# SCU_PCIe.net
KiCad netlist of a schematic drawn in Altium Designer
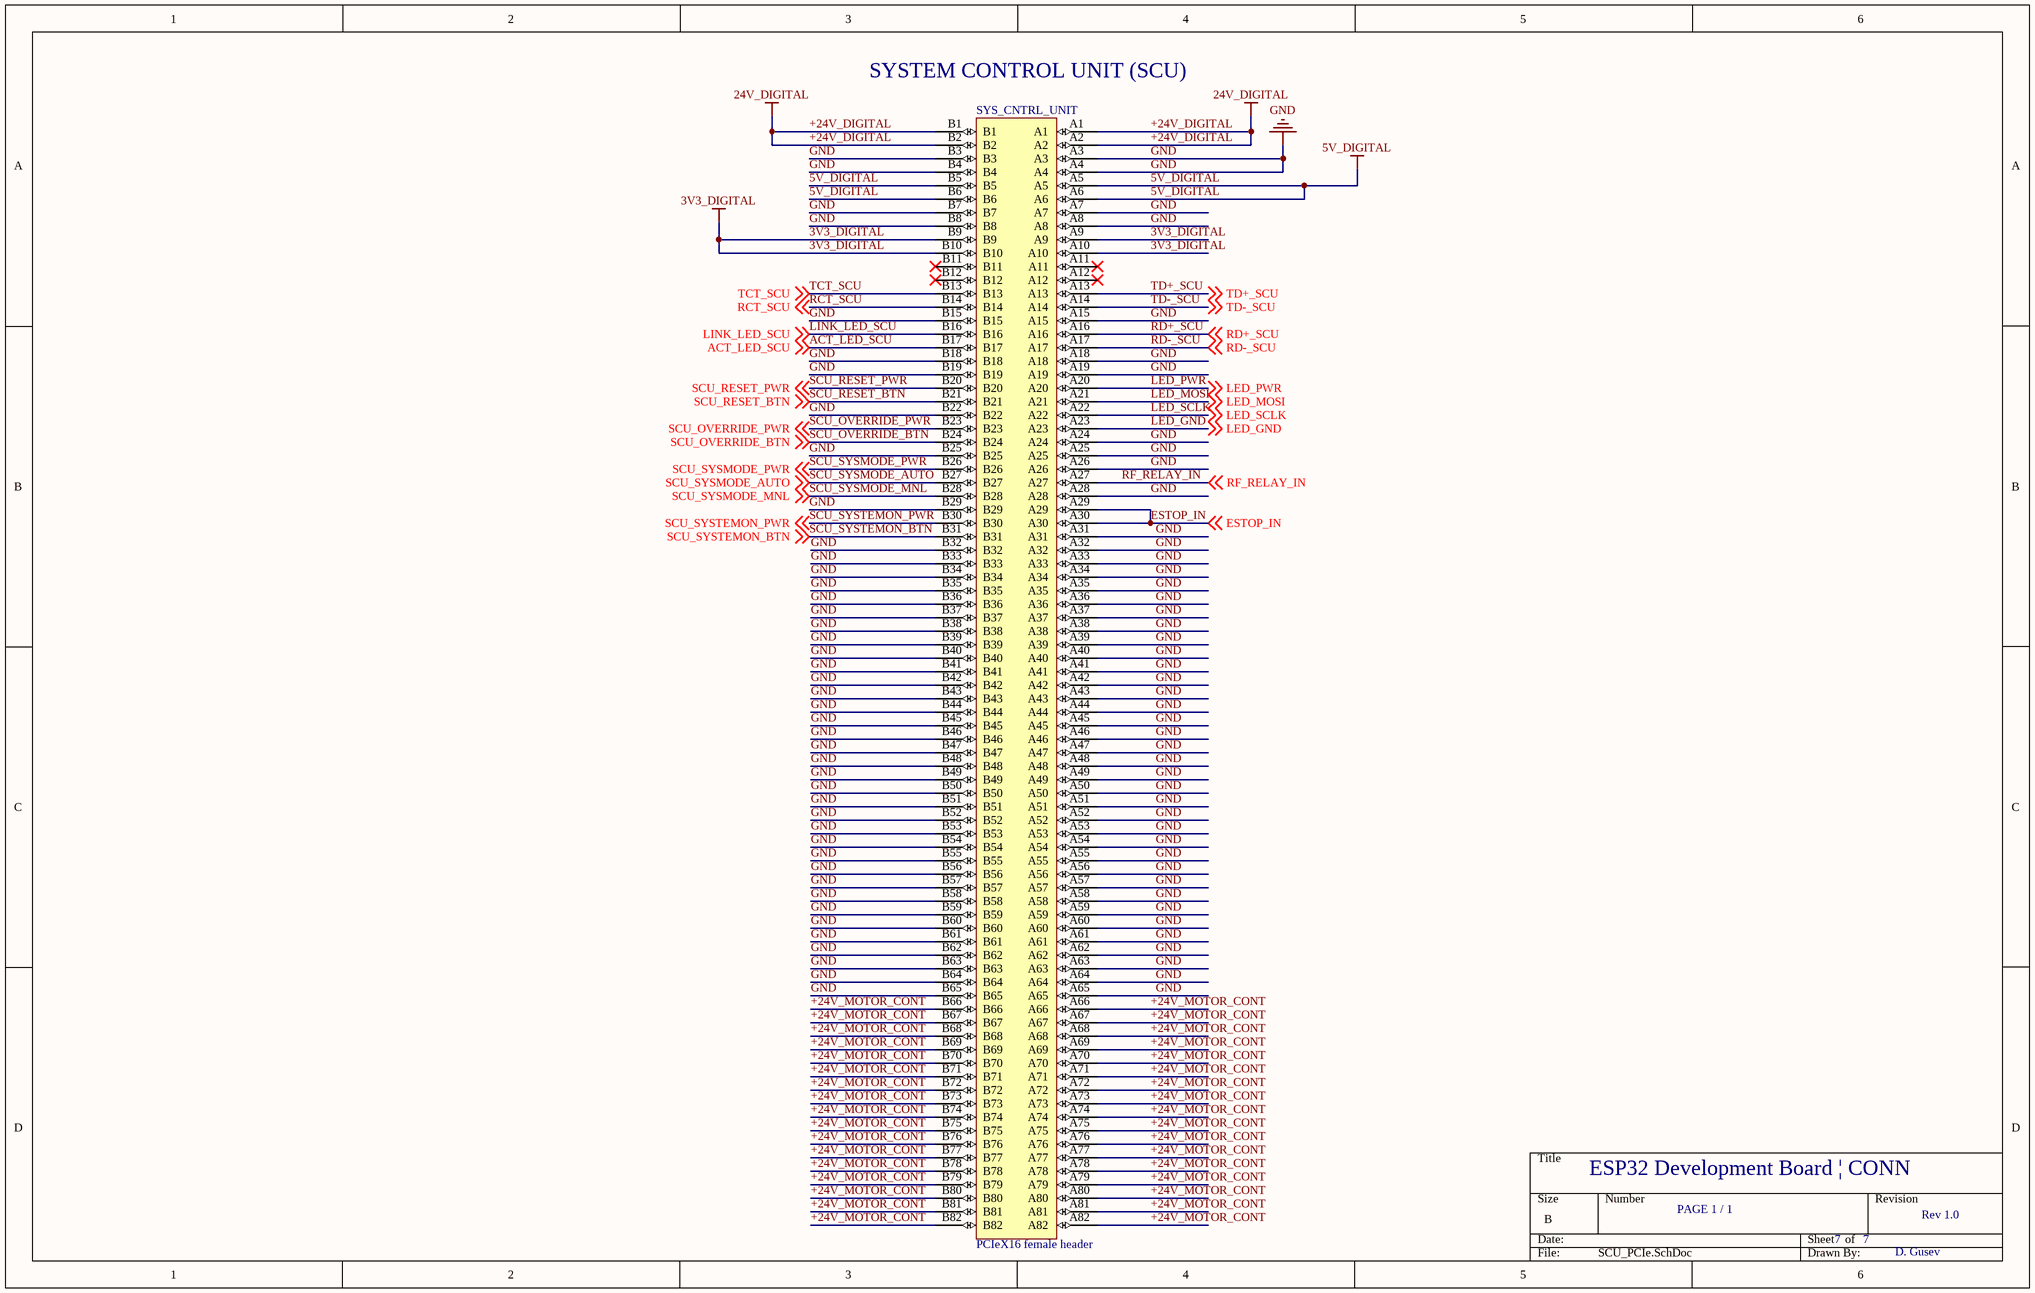
[diagram p0: SCU_PCIe.SchDoc]

(export (version "E")
  (design (tool "Eeschema 10.0.6"))
  (components
    (comp (ref "SYS_CNTRL_UNIT")
      (value "PCIeX16 female header")
      (footprint "SAMTEC_PCIE-164-02-X-D-TH")
      (description "164-position SAMTEC female header")
      (libsource (lib "ANTS-MotherBoard-B1") (part "PCIeX16 female header"))
    )
  )
  (nets
    (net (code "1") (name "/+24V_MOTOR_CONT") (class "Default")
      (node (ref "SYS_CNTRL_UNIT") (pin "A66") (pinfunction "A66_A66") (pintype "bidirectional"))
      (node (ref "SYS_CNTRL_UNIT") (pin "A67") (pinfunction "A67_A67") (pintype "bidirectional"))
      (node (ref "SYS_CNTRL_UNIT") (pin "A68") (pinfunction "A68_A68") (pintype "bidirectional"))
      (node (ref "SYS_CNTRL_UNIT") (pin "A69") (pinfunction "A69_A69") (pintype "bidirectional"))
      (node (ref "SYS_CNTRL_UNIT") (pin "A70") (pinfunction "A70_A70") (pintype "bidirectional"))
      (node (ref "SYS_CNTRL_UNIT") (pin "A71") (pinfunction "A71_A71") (pintype "bidirectional"))
      (node (ref "SYS_CNTRL_UNIT") (pin "A72") (pinfunction "A72_A72") (pintype "bidirectional"))
      (node (ref "SYS_CNTRL_UNIT") (pin "A73") (pinfunction "A73_A73") (pintype "bidirectional"))
      (node (ref "SYS_CNTRL_UNIT") (pin "A74") (pinfunction "A74_A74") (pintype "bidirectional"))
      (node (ref "SYS_CNTRL_UNIT") (pin "A75") (pinfunction "A75_A75") (pintype "bidirectional"))
      (node (ref "SYS_CNTRL_UNIT") (pin "A76") (pinfunction "A76_A76") (pintype "bidirectional"))
      (node (ref "SYS_CNTRL_UNIT") (pin "A77") (pinfunction "A77_A77") (pintype "bidirectional"))
      (node (ref "SYS_CNTRL_UNIT") (pin "A78") (pinfunction "A78_A78") (pintype "bidirectional"))
      (node (ref "SYS_CNTRL_UNIT") (pin "A79") (pinfunction "A79_A79") (pintype "bidirectional"))
      (node (ref "SYS_CNTRL_UNIT") (pin "A80") (pinfunction "A80_A80") (pintype "bidirectional"))
      (node (ref "SYS_CNTRL_UNIT") (pin "A81") (pinfunction "A81_A81") (pintype "bidirectional"))
      (node (ref "SYS_CNTRL_UNIT") (pin "A82") (pinfunction "A82_A82") (pintype "bidirectional"))
      (node (ref "SYS_CNTRL_UNIT") (pin "B66") (pinfunction "B66_B66") (pintype "bidirectional"))
      (node (ref "SYS_CNTRL_UNIT") (pin "B67") (pinfunction "B67_B67") (pintype "bidirectional"))
      (node (ref "SYS_CNTRL_UNIT") (pin "B68") (pinfunction "B68_B68") (pintype "bidirectional"))
      (node (ref "SYS_CNTRL_UNIT") (pin "B69") (pinfunction "B69_B69") (pintype "bidirectional"))
      (node (ref "SYS_CNTRL_UNIT") (pin "B70") (pinfunction "B70_B70") (pintype "bidirectional"))
      (node (ref "SYS_CNTRL_UNIT") (pin "B71") (pinfunction "B71_B71") (pintype "bidirectional"))
      (node (ref "SYS_CNTRL_UNIT") (pin "B72") (pinfunction "B72_B72") (pintype "bidirectional"))
      (node (ref "SYS_CNTRL_UNIT") (pin "B73") (pinfunction "B73_B73") (pintype "bidirectional"))
      (node (ref "SYS_CNTRL_UNIT") (pin "B74") (pinfunction "B74_B74") (pintype "bidirectional"))
      (node (ref "SYS_CNTRL_UNIT") (pin "B75") (pinfunction "B75_B75") (pintype "bidirectional"))
      (node (ref "SYS_CNTRL_UNIT") (pin "B76") (pinfunction "B76_B76") (pintype "bidirectional"))
      (node (ref "SYS_CNTRL_UNIT") (pin "B77") (pinfunction "B77_B77") (pintype "bidirectional"))
      (node (ref "SYS_CNTRL_UNIT") (pin "B78") (pinfunction "B78_B78") (pintype "bidirectional"))
      (node (ref "SYS_CNTRL_UNIT") (pin "B79") (pinfunction "B79_B79") (pintype "bidirectional"))
      (node (ref "SYS_CNTRL_UNIT") (pin "B80") (pinfunction "B80_B80") (pintype "bidirectional"))
      (node (ref "SYS_CNTRL_UNIT") (pin "B81") (pinfunction "B81_B81") (pintype "bidirectional"))
      (node (ref "SYS_CNTRL_UNIT") (pin "B82") (pinfunction "B82_B82") (pintype "bidirectional"))
    )
    (net (code "2") (name "3V3_DIGITAL") (class "Default")
      (node (ref "SYS_CNTRL_UNIT") (pin "A10") (pinfunction "A10_A10") (pintype "bidirectional"))
      (node (ref "SYS_CNTRL_UNIT") (pin "A9") (pinfunction "A9_A9") (pintype "bidirectional"))
      (node (ref "SYS_CNTRL_UNIT") (pin "B10") (pinfunction "B10_B10") (pintype "bidirectional"))
      (node (ref "SYS_CNTRL_UNIT") (pin "B9") (pinfunction "B9_B9") (pintype "bidirectional"))
    )
    (net (code "3") (name "5V_DIGITAL") (class "Default")
      (node (ref "SYS_CNTRL_UNIT") (pin "A5") (pinfunction "A5_A5") (pintype "bidirectional"))
      (node (ref "SYS_CNTRL_UNIT") (pin "A6") (pinfunction "A6_A6") (pintype "bidirectional"))
      (node (ref "SYS_CNTRL_UNIT") (pin "B5") (pinfunction "B5_B5") (pintype "bidirectional"))
      (node (ref "SYS_CNTRL_UNIT") (pin "B6") (pinfunction "B6_B6") (pintype "bidirectional"))
    )
    (net (code "4") (name "24V_DIGITAL") (class "Default")
      (node (ref "SYS_CNTRL_UNIT") (pin "A1") (pinfunction "A1_A1") (pintype "bidirectional"))
      (node (ref "SYS_CNTRL_UNIT") (pin "A2") (pinfunction "A2_A2") (pintype "bidirectional"))
      (node (ref "SYS_CNTRL_UNIT") (pin "B1") (pinfunction "B1_B1") (pintype "bidirectional"))
      (node (ref "SYS_CNTRL_UNIT") (pin "B2") (pinfunction "B2_B2") (pintype "bidirectional"))
    )
    (net (code "5") (name "ACT_LED_SCU") (class "Default")
      (node (ref "SYS_CNTRL_UNIT") (pin "B17") (pinfunction "B17_B17") (pintype "bidirectional"))
    )
    (net (code "6") (name "ESTOP_IN") (class "Default")
      (node (ref "SYS_CNTRL_UNIT") (pin "A29") (pinfunction "A29_A29") (pintype "bidirectional"))
      (node (ref "SYS_CNTRL_UNIT") (pin "A30") (pinfunction "A30_A30") (pintype "bidirectional"))
    )
    (net (code "7") (name "GND") (class "Default")
      (node (ref "SYS_CNTRL_UNIT") (pin "A15") (pinfunction "A15_A15") (pintype "bidirectional"))
      (node (ref "SYS_CNTRL_UNIT") (pin "A18") (pinfunction "A18_A18") (pintype "bidirectional"))
      (node (ref "SYS_CNTRL_UNIT") (pin "A19") (pinfunction "A19_A19") (pintype "bidirectional"))
      (node (ref "SYS_CNTRL_UNIT") (pin "A24") (pinfunction "A24_A24") (pintype "bidirectional"))
      (node (ref "SYS_CNTRL_UNIT") (pin "A25") (pinfunction "A25_A25") (pintype "bidirectional"))
      (node (ref "SYS_CNTRL_UNIT") (pin "A26") (pinfunction "A26_A26") (pintype "bidirectional"))
      (node (ref "SYS_CNTRL_UNIT") (pin "A28") (pinfunction "A28_A28") (pintype "bidirectional"))
      (node (ref "SYS_CNTRL_UNIT") (pin "A3") (pinfunction "A3_A3") (pintype "bidirectional"))
      (node (ref "SYS_CNTRL_UNIT") (pin "A31") (pinfunction "A31_A31") (pintype "bidirectional"))
      (node (ref "SYS_CNTRL_UNIT") (pin "A32") (pinfunction "A32_A32") (pintype "bidirectional"))
      (node (ref "SYS_CNTRL_UNIT") (pin "A33") (pinfunction "A33_A33") (pintype "bidirectional"))
      (node (ref "SYS_CNTRL_UNIT") (pin "A34") (pinfunction "A34_A34") (pintype "bidirectional"))
      (node (ref "SYS_CNTRL_UNIT") (pin "A35") (pinfunction "A35_A35") (pintype "bidirectional"))
      (node (ref "SYS_CNTRL_UNIT") (pin "A36") (pinfunction "A36_A36") (pintype "bidirectional"))
      (node (ref "SYS_CNTRL_UNIT") (pin "A37") (pinfunction "A37_A37") (pintype "bidirectional"))
      (node (ref "SYS_CNTRL_UNIT") (pin "A38") (pinfunction "A38_A38") (pintype "bidirectional"))
      (node (ref "SYS_CNTRL_UNIT") (pin "A39") (pinfunction "A39_A39") (pintype "bidirectional"))
      (node (ref "SYS_CNTRL_UNIT") (pin "A4") (pinfunction "A4_A4") (pintype "bidirectional"))
      (node (ref "SYS_CNTRL_UNIT") (pin "A40") (pinfunction "A40_A40") (pintype "bidirectional"))
      (node (ref "SYS_CNTRL_UNIT") (pin "A41") (pinfunction "A41_A41") (pintype "bidirectional"))
      (node (ref "SYS_CNTRL_UNIT") (pin "A42") (pinfunction "A42_A42") (pintype "bidirectional"))
      (node (ref "SYS_CNTRL_UNIT") (pin "A43") (pinfunction "A43_A43") (pintype "bidirectional"))
      (node (ref "SYS_CNTRL_UNIT") (pin "A44") (pinfunction "A44_A44") (pintype "bidirectional"))
      (node (ref "SYS_CNTRL_UNIT") (pin "A45") (pinfunction "A45_A45") (pintype "bidirectional"))
      (node (ref "SYS_CNTRL_UNIT") (pin "A46") (pinfunction "A46_A46") (pintype "bidirectional"))
      (node (ref "SYS_CNTRL_UNIT") (pin "A47") (pinfunction "A47_A47") (pintype "bidirectional"))
      (node (ref "SYS_CNTRL_UNIT") (pin "A48") (pinfunction "A48_A48") (pintype "bidirectional"))
      (node (ref "SYS_CNTRL_UNIT") (pin "A49") (pinfunction "A49_A49") (pintype "bidirectional"))
      (node (ref "SYS_CNTRL_UNIT") (pin "A50") (pinfunction "A50_A50") (pintype "bidirectional"))
      (node (ref "SYS_CNTRL_UNIT") (pin "A51") (pinfunction "A51_A51") (pintype "bidirectional"))
      (node (ref "SYS_CNTRL_UNIT") (pin "A52") (pinfunction "A52_A52") (pintype "bidirectional"))
      (node (ref "SYS_CNTRL_UNIT") (pin "A53") (pinfunction "A53_A53") (pintype "bidirectional"))
      (node (ref "SYS_CNTRL_UNIT") (pin "A54") (pinfunction "A54_A54") (pintype "bidirectional"))
      (node (ref "SYS_CNTRL_UNIT") (pin "A55") (pinfunction "A55_A55") (pintype "bidirectional"))
      (node (ref "SYS_CNTRL_UNIT") (pin "A56") (pinfunction "A56_A56") (pintype "bidirectional"))
      (node (ref "SYS_CNTRL_UNIT") (pin "A57") (pinfunction "A57_A57") (pintype "bidirectional"))
      (node (ref "SYS_CNTRL_UNIT") (pin "A58") (pinfunction "A58_A58") (pintype "bidirectional"))
      (node (ref "SYS_CNTRL_UNIT") (pin "A59") (pinfunction "A59_A59") (pintype "bidirectional"))
      (node (ref "SYS_CNTRL_UNIT") (pin "A60") (pinfunction "A60_A60") (pintype "bidirectional"))
      (node (ref "SYS_CNTRL_UNIT") (pin "A61") (pinfunction "A61_A61") (pintype "bidirectional"))
      (node (ref "SYS_CNTRL_UNIT") (pin "A62") (pinfunction "A62_A62") (pintype "bidirectional"))
      (node (ref "SYS_CNTRL_UNIT") (pin "A63") (pinfunction "A63_A63") (pintype "bidirectional"))
      (node (ref "SYS_CNTRL_UNIT") (pin "A64") (pinfunction "A64_A64") (pintype "bidirectional"))
      (node (ref "SYS_CNTRL_UNIT") (pin "A65") (pinfunction "A65_A65") (pintype "bidirectional"))
      (node (ref "SYS_CNTRL_UNIT") (pin "A7") (pinfunction "A7_A7") (pintype "bidirectional"))
      (node (ref "SYS_CNTRL_UNIT") (pin "A8") (pinfunction "A8_A8") (pintype "bidirectional"))
      (node (ref "SYS_CNTRL_UNIT") (pin "B15") (pinfunction "B15_B15") (pintype "bidirectional"))
      (node (ref "SYS_CNTRL_UNIT") (pin "B18") (pinfunction "B18_B18") (pintype "bidirectional"))
      (node (ref "SYS_CNTRL_UNIT") (pin "B19") (pinfunction "B19_B19") (pintype "bidirectional"))
      (node (ref "SYS_CNTRL_UNIT") (pin "B22") (pinfunction "B22_B22") (pintype "bidirectional"))
      (node (ref "SYS_CNTRL_UNIT") (pin "B25") (pinfunction "B25_B25") (pintype "bidirectional"))
      (node (ref "SYS_CNTRL_UNIT") (pin "B29") (pinfunction "B29_B29") (pintype "bidirectional"))
      (node (ref "SYS_CNTRL_UNIT") (pin "B3") (pinfunction "B3_B3") (pintype "bidirectional"))
      (node (ref "SYS_CNTRL_UNIT") (pin "B32") (pinfunction "B32_B32") (pintype "bidirectional"))
      (node (ref "SYS_CNTRL_UNIT") (pin "B33") (pinfunction "B33_B33") (pintype "bidirectional"))
      (node (ref "SYS_CNTRL_UNIT") (pin "B34") (pinfunction "B34_B34") (pintype "bidirectional"))
      (node (ref "SYS_CNTRL_UNIT") (pin "B35") (pinfunction "B35_B35") (pintype "bidirectional"))
      (node (ref "SYS_CNTRL_UNIT") (pin "B36") (pinfunction "B36_B36") (pintype "bidirectional"))
      (node (ref "SYS_CNTRL_UNIT") (pin "B37") (pinfunction "B37_B37") (pintype "bidirectional"))
      (node (ref "SYS_CNTRL_UNIT") (pin "B38") (pinfunction "B38_B38") (pintype "bidirectional"))
      (node (ref "SYS_CNTRL_UNIT") (pin "B39") (pinfunction "B39_B39") (pintype "bidirectional"))
      (node (ref "SYS_CNTRL_UNIT") (pin "B4") (pinfunction "B4_B4") (pintype "bidirectional"))
      (node (ref "SYS_CNTRL_UNIT") (pin "B40") (pinfunction "B40_B40") (pintype "bidirectional"))
      (node (ref "SYS_CNTRL_UNIT") (pin "B41") (pinfunction "B41_B41") (pintype "bidirectional"))
      (node (ref "SYS_CNTRL_UNIT") (pin "B42") (pinfunction "B42_B42") (pintype "bidirectional"))
      (node (ref "SYS_CNTRL_UNIT") (pin "B43") (pinfunction "B43_B43") (pintype "bidirectional"))
      (node (ref "SYS_CNTRL_UNIT") (pin "B44") (pinfunction "B44_B44") (pintype "bidirectional"))
      (node (ref "SYS_CNTRL_UNIT") (pin "B45") (pinfunction "B45_B45") (pintype "bidirectional"))
      (node (ref "SYS_CNTRL_UNIT") (pin "B46") (pinfunction "B46_B46") (pintype "bidirectional"))
      (node (ref "SYS_CNTRL_UNIT") (pin "B47") (pinfunction "B47_B47") (pintype "bidirectional"))
      (node (ref "SYS_CNTRL_UNIT") (pin "B48") (pinfunction "B48_B48") (pintype "bidirectional"))
      (node (ref "SYS_CNTRL_UNIT") (pin "B49") (pinfunction "B49_B49") (pintype "bidirectional"))
      (node (ref "SYS_CNTRL_UNIT") (pin "B50") (pinfunction "B50_B50") (pintype "bidirectional"))
      (node (ref "SYS_CNTRL_UNIT") (pin "B51") (pinfunction "B51_B51") (pintype "bidirectional"))
      (node (ref "SYS_CNTRL_UNIT") (pin "B52") (pinfunction "B52_B52") (pintype "bidirectional"))
      (node (ref "SYS_CNTRL_UNIT") (pin "B53") (pinfunction "B53_B53") (pintype "bidirectional"))
      (node (ref "SYS_CNTRL_UNIT") (pin "B54") (pinfunction "B54_B54") (pintype "bidirectional"))
      (node (ref "SYS_CNTRL_UNIT") (pin "B55") (pinfunction "B55_B55") (pintype "bidirectional"))
      (node (ref "SYS_CNTRL_UNIT") (pin "B56") (pinfunction "B56_B56") (pintype "bidirectional"))
      (node (ref "SYS_CNTRL_UNIT") (pin "B57") (pinfunction "B57_B57") (pintype "bidirectional"))
      (node (ref "SYS_CNTRL_UNIT") (pin "B58") (pinfunction "B58_B58") (pintype "bidirectional"))
      (node (ref "SYS_CNTRL_UNIT") (pin "B59") (pinfunction "B59_B59") (pintype "bidirectional"))
      (node (ref "SYS_CNTRL_UNIT") (pin "B60") (pinfunction "B60_B60") (pintype "bidirectional"))
      (node (ref "SYS_CNTRL_UNIT") (pin "B61") (pinfunction "B61_B61") (pintype "bidirectional"))
      (node (ref "SYS_CNTRL_UNIT") (pin "B62") (pinfunction "B62_B62") (pintype "bidirectional"))
      (node (ref "SYS_CNTRL_UNIT") (pin "B63") (pinfunction "B63_B63") (pintype "bidirectional"))
      (node (ref "SYS_CNTRL_UNIT") (pin "B64") (pinfunction "B64_B64") (pintype "bidirectional"))
      (node (ref "SYS_CNTRL_UNIT") (pin "B65") (pinfunction "B65_B65") (pintype "bidirectional"))
      (node (ref "SYS_CNTRL_UNIT") (pin "B7") (pinfunction "B7_B7") (pintype "bidirectional"))
      (node (ref "SYS_CNTRL_UNIT") (pin "B8") (pinfunction "B8_B8") (pintype "bidirectional"))
    )
    (net (code "8") (name "LED_GND") (class "Default")
      (node (ref "SYS_CNTRL_UNIT") (pin "A23") (pinfunction "A23_A23") (pintype "bidirectional"))
    )
    (net (code "9") (name "LED_MOSI") (class "Default")
      (node (ref "SYS_CNTRL_UNIT") (pin "A21") (pinfunction "A21_A21") (pintype "bidirectional"))
    )
    (net (code "10") (name "LED_PWR") (class "Default")
      (node (ref "SYS_CNTRL_UNIT") (pin "A20") (pinfunction "A20_A20") (pintype "bidirectional"))
    )
    (net (code "11") (name "LED_SCLK") (class "Default")
      (node (ref "SYS_CNTRL_UNIT") (pin "A22") (pinfunction "A22_A22") (pintype "bidirectional"))
    )
    (net (code "12") (name "LINK_LED_SCU") (class "Default")
      (node (ref "SYS_CNTRL_UNIT") (pin "B16") (pinfunction "B16_B16") (pintype "bidirectional"))
    )
    (net (code "13") (name "RCT_SCU") (class "Default")
      (node (ref "SYS_CNTRL_UNIT") (pin "B14") (pinfunction "B14_B14") (pintype "bidirectional"))
    )
    (net (code "14") (name "RD+_SCU") (class "Default")
      (node (ref "SYS_CNTRL_UNIT") (pin "A16") (pinfunction "A16_A16") (pintype "bidirectional"))
    )
    (net (code "15") (name "RD-_SCU") (class "Default")
      (node (ref "SYS_CNTRL_UNIT") (pin "A17") (pinfunction "A17_A17") (pintype "bidirectional"))
    )
    (net (code "16") (name "RF_RELAY_IN") (class "Default")
      (node (ref "SYS_CNTRL_UNIT") (pin "A27") (pinfunction "A27_A27") (pintype "bidirectional"))
    )
    (net (code "17") (name "SCU_OVERRIDE_BTN") (class "Default")
      (node (ref "SYS_CNTRL_UNIT") (pin "B24") (pinfunction "B24_B24") (pintype "bidirectional"))
    )
    (net (code "18") (name "SCU_OVERRIDE_PWR") (class "Default")
      (node (ref "SYS_CNTRL_UNIT") (pin "B23") (pinfunction "B23_B23") (pintype "bidirectional"))
    )
    (net (code "19") (name "SCU_RESET_BTN") (class "Default")
      (node (ref "SYS_CNTRL_UNIT") (pin "B21") (pinfunction "B21_B21") (pintype "bidirectional"))
    )
    (net (code "20") (name "SCU_RESET_PWR") (class "Default")
      (node (ref "SYS_CNTRL_UNIT") (pin "B20") (pinfunction "B20_B20") (pintype "bidirectional"))
    )
    (net (code "21") (name "SCU_SYSMODE_AUTO") (class "Default")
      (node (ref "SYS_CNTRL_UNIT") (pin "B27") (pinfunction "B27_B27") (pintype "bidirectional"))
    )
    (net (code "22") (name "SCU_SYSMODE_MNL") (class "Default")
      (node (ref "SYS_CNTRL_UNIT") (pin "B28") (pinfunction "B28_B28") (pintype "bidirectional"))
    )
    (net (code "23") (name "SCU_SYSMODE_PWR") (class "Default")
      (node (ref "SYS_CNTRL_UNIT") (pin "B26") (pinfunction "B26_B26") (pintype "bidirectional"))
    )
    (net (code "24") (name "SCU_SYSTEMON_BTN") (class "Default")
      (node (ref "SYS_CNTRL_UNIT") (pin "B31") (pinfunction "B31_B31") (pintype "bidirectional"))
    )
    (net (code "25") (name "SCU_SYSTEMON_PWR") (class "Default")
      (node (ref "SYS_CNTRL_UNIT") (pin "B30") (pinfunction "B30_B30") (pintype "bidirectional"))
    )
    (net (code "26") (name "TCT_SCU") (class "Default")
      (node (ref "SYS_CNTRL_UNIT") (pin "B13") (pinfunction "B13_B13") (pintype "bidirectional"))
    )
    (net (code "27") (name "TD+_SCU") (class "Default")
      (node (ref "SYS_CNTRL_UNIT") (pin "A13") (pinfunction "A13_A13") (pintype "bidirectional"))
    )
    (net (code "28") (name "TD-_SCU") (class "Default")
      (node (ref "SYS_CNTRL_UNIT") (pin "A14") (pinfunction "A14_A14") (pintype "bidirectional"))
    )
    (net (code "29") (name "unconnected-(SYS_CNTRL_UNIT-PadA11)") (class "Default")
      (node (ref "SYS_CNTRL_UNIT") (pin "A11") (pinfunction "A11_A11") (pintype "bidirectional+no_connect"))
    )
    (net (code "30") (name "unconnected-(SYS_CNTRL_UNIT-PadA12)") (class "Default")
      (node (ref "SYS_CNTRL_UNIT") (pin "A12") (pinfunction "A12_A12") (pintype "bidirectional+no_connect"))
    )
    (net (code "31") (name "unconnected-(SYS_CNTRL_UNIT-PadB11)") (class "Default")
      (node (ref "SYS_CNTRL_UNIT") (pin "B11") (pinfunction "B11_B11") (pintype "bidirectional+no_connect"))
    )
    (net (code "32") (name "unconnected-(SYS_CNTRL_UNIT-PadB12)") (class "Default")
      (node (ref "SYS_CNTRL_UNIT") (pin "B12") (pinfunction "B12_B12") (pintype "bidirectional+no_connect"))
    )
  )
)
